# 5VPart.net
KiCad netlist of a schematic drawn in EAGLE
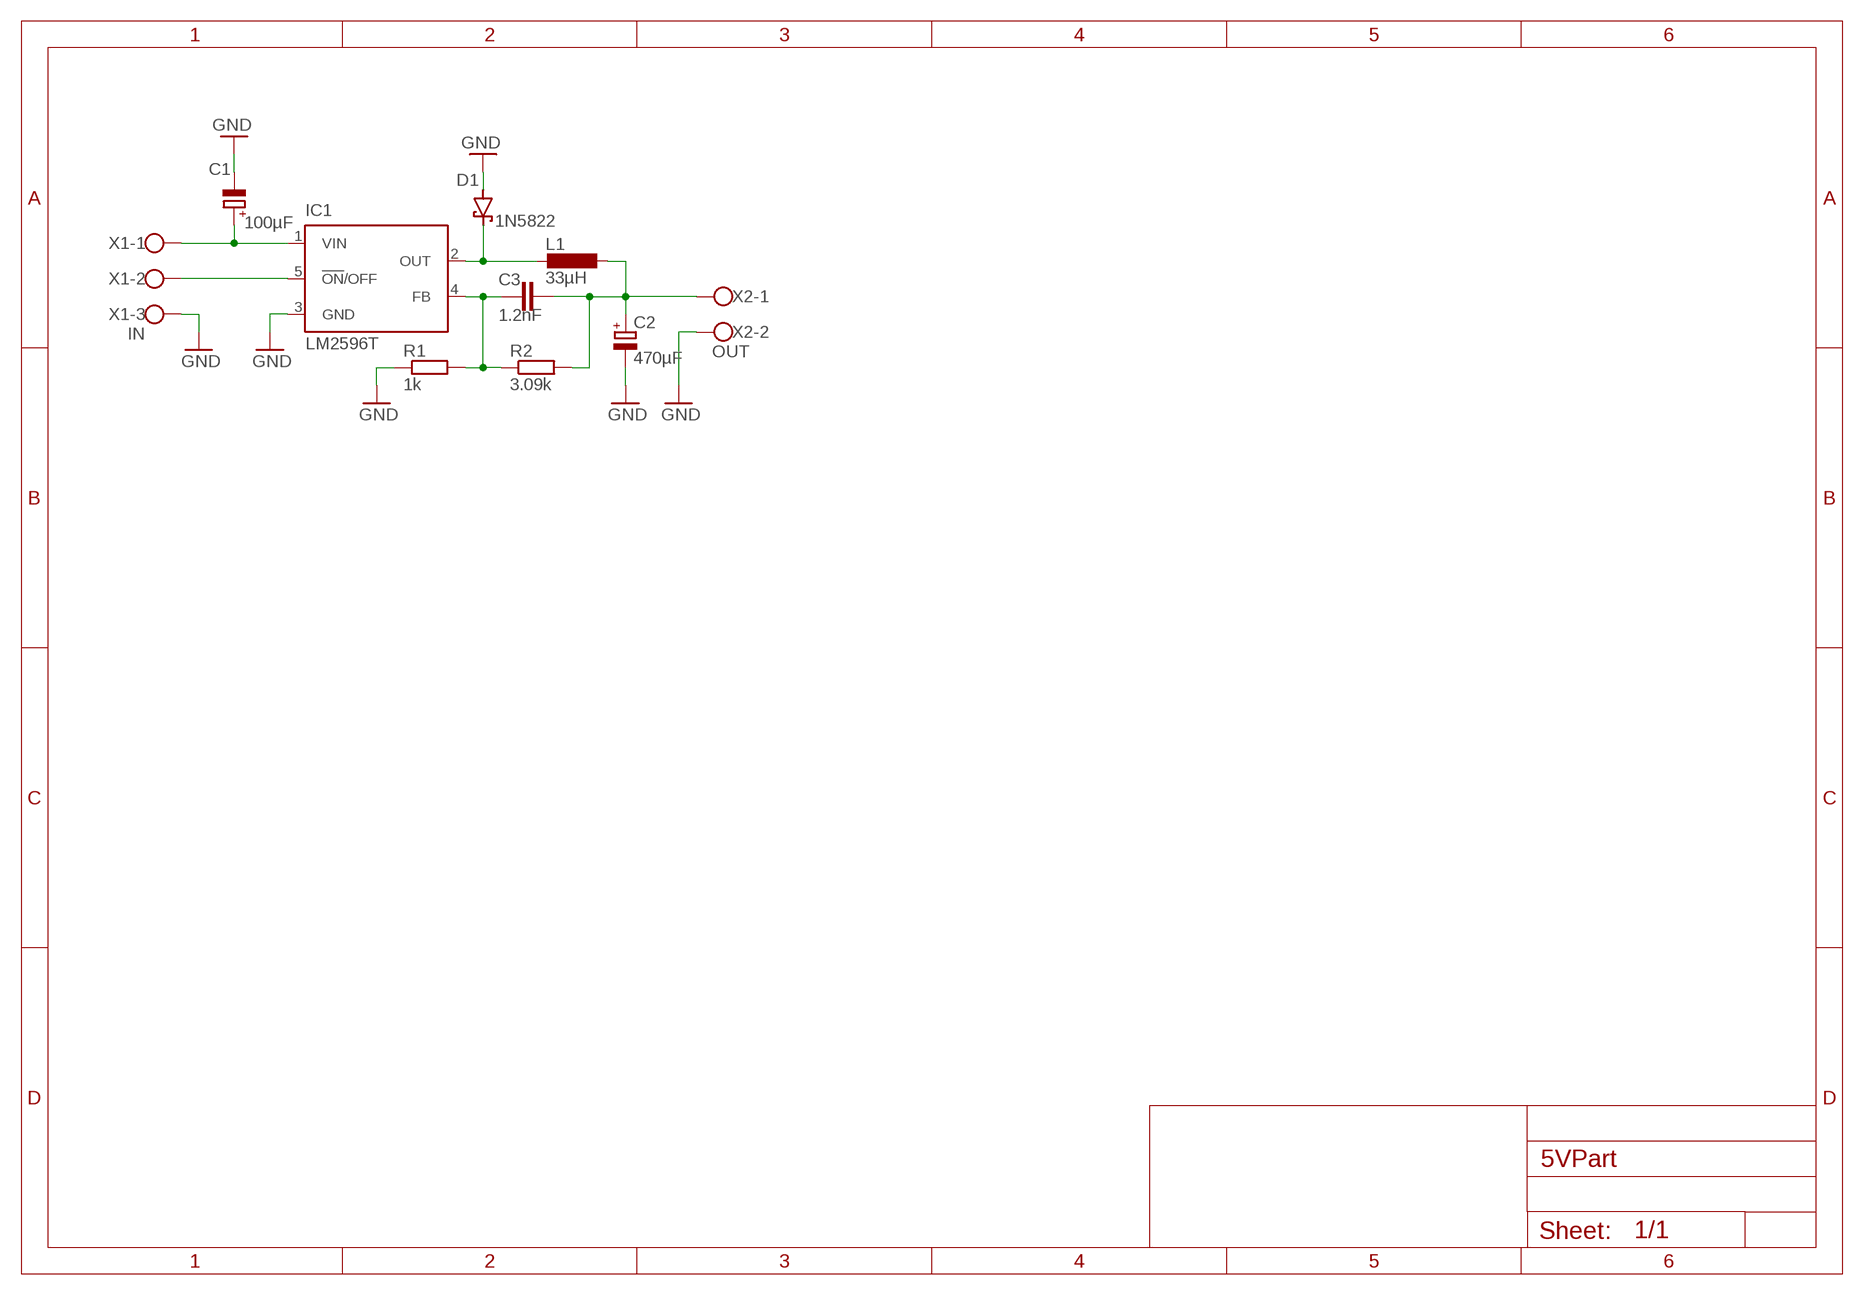
[diagram p0: schematic, sheet 1]

(export (version "E")
  (design (tool "Eeschema 10.0.6"))
  (components
    (comp (ref "C1")
      (value "100µF")
      (footprint "eagle-import:E2,5-6")
      (libsource (lib "eagle-import") (part "CPOL-EUE2.5-6"))
    )
    (comp (ref "C2")
      (value "470µF")
      (footprint "eagle-import:E2,5-6")
      (libsource (lib "eagle-import") (part "CPOL-EUE2.5-6"))
    )
    (comp (ref "C3")
      (value "1.2nF")
      (footprint "eagle-import:C050-024X044")
      (libsource (lib "eagle-import") (part "C-EU050-024X044"))
    )
    (comp (ref "D1")
      (value "1N5822")
      (footprint "eagle-import:C4111-15")
      (libsource (lib "eagle-import") (part "SCHOTTKY-DIODEC4111-15"))
    )
    (comp (ref "IC1")
      (value "LM2596T")
      (footprint "eagle-import:T05D")
      (fields (field (name "MPN") "LM2596T-ADJ/LF02"))
      (libsource (lib "eagle-import") (part "LM2596T"))
    )
    (comp (ref "L1")
      (value "33µH")
      (footprint "eagle-import:TJ3-U2")
      (libsource (lib "eagle-import") (part "L-EUTJ3-U2"))
    )
    (comp (ref "R1")
      (value "1k")
      (footprint "eagle-import:0207_10")
      (libsource (lib "eagle-import") (part "R-EU_0207/10"))
    )
    (comp (ref "R2")
      (value "3.09k")
      (footprint "eagle-import:0207_10")
      (libsource (lib "eagle-import") (part "R-EU_0207/10"))
    )
    (comp (ref "X1")
      (value "IN")
      (footprint "eagle-import:W237-103")
      (fields (field (name "MPN") "237-103"))
      (libsource (lib "eagle-import") (part "W237-103"))
    )
    (comp (ref "X2")
      (value "OUT")
      (footprint "eagle-import:W237-102")
      (fields (field (name "MPN") "237-102"))
      (libsource (lib "eagle-import") (part "W237-102"))
    )
  )
  (nets
    (net (code "1") (name "GND") (class "Default")
      (node (ref "C1") (pin "-") (pinfunction "-_-") (pintype "passive"))
      (node (ref "C2") (pin "-") (pinfunction "-_-") (pintype "passive"))
      (node (ref "D1") (pin "A") (pinfunction "A_A") (pintype "passive"))
      (node (ref "IC1") (pin "3") (pinfunction "GND_3") (pintype "power_in"))
      (node (ref "R1") (pin "1") (pinfunction "1_1") (pintype "passive"))
      (node (ref "X1") (pin "3") (pinfunction "KL_3") (pintype "passive"))
      (node (ref "X2") (pin "2") (pinfunction "KL_2") (pintype "passive"))
    )
    (net (code "2") (name "Net-(IC1-FB)") (class "Default")
      (node (ref "C3") (pin "1") (pinfunction "1_1") (pintype "passive"))
      (node (ref "IC1") (pin "4") (pinfunction "FB_4") (pintype "input"))
      (node (ref "R1") (pin "2") (pinfunction "2_2") (pintype "passive"))
      (node (ref "R2") (pin "1") (pinfunction "1_1") (pintype "passive"))
    )
    (net (code "3") (name "Net-(IC1-OUT)") (class "Default")
      (node (ref "D1") (pin "C") (pinfunction "C_C") (pintype "passive"))
      (node (ref "IC1") (pin "2") (pinfunction "OUT_2") (pintype "output"))
      (node (ref "L1") (pin "2") (pinfunction "2_2") (pintype "passive"))
    )
    (net (code "4") (name "Net-(IC1-VIN)") (class "Default")
      (node (ref "C1") (pin "+") (pinfunction "+_+") (pintype "passive"))
      (node (ref "IC1") (pin "1") (pinfunction "VIN_1") (pintype "input"))
      (node (ref "X1") (pin "1") (pinfunction "KL_1") (pintype "passive"))
    )
    (net (code "5") (name "Net-(IC1-~{ON}{slash}OFF)") (class "Default")
      (node (ref "IC1") (pin "5") (pinfunction "~{ON}/OFF_5") (pintype "input"))
      (node (ref "X1") (pin "2") (pinfunction "KL_2") (pintype "passive"))
    )
    (net (code "6") (name "Net-(X2A-KL)") (class "Default")
      (node (ref "C2") (pin "+") (pinfunction "+_+") (pintype "passive"))
      (node (ref "C3") (pin "2") (pinfunction "2_2") (pintype "passive"))
      (node (ref "L1") (pin "1") (pinfunction "1_1") (pintype "passive"))
      (node (ref "R2") (pin "2") (pinfunction "2_2") (pintype "passive"))
      (node (ref "X2") (pin "1") (pinfunction "KL_1") (pintype "passive"))
    )
  )
)
